# InverterSchematic.net
KiCad netlist of a schematic drawn in Altium Designer
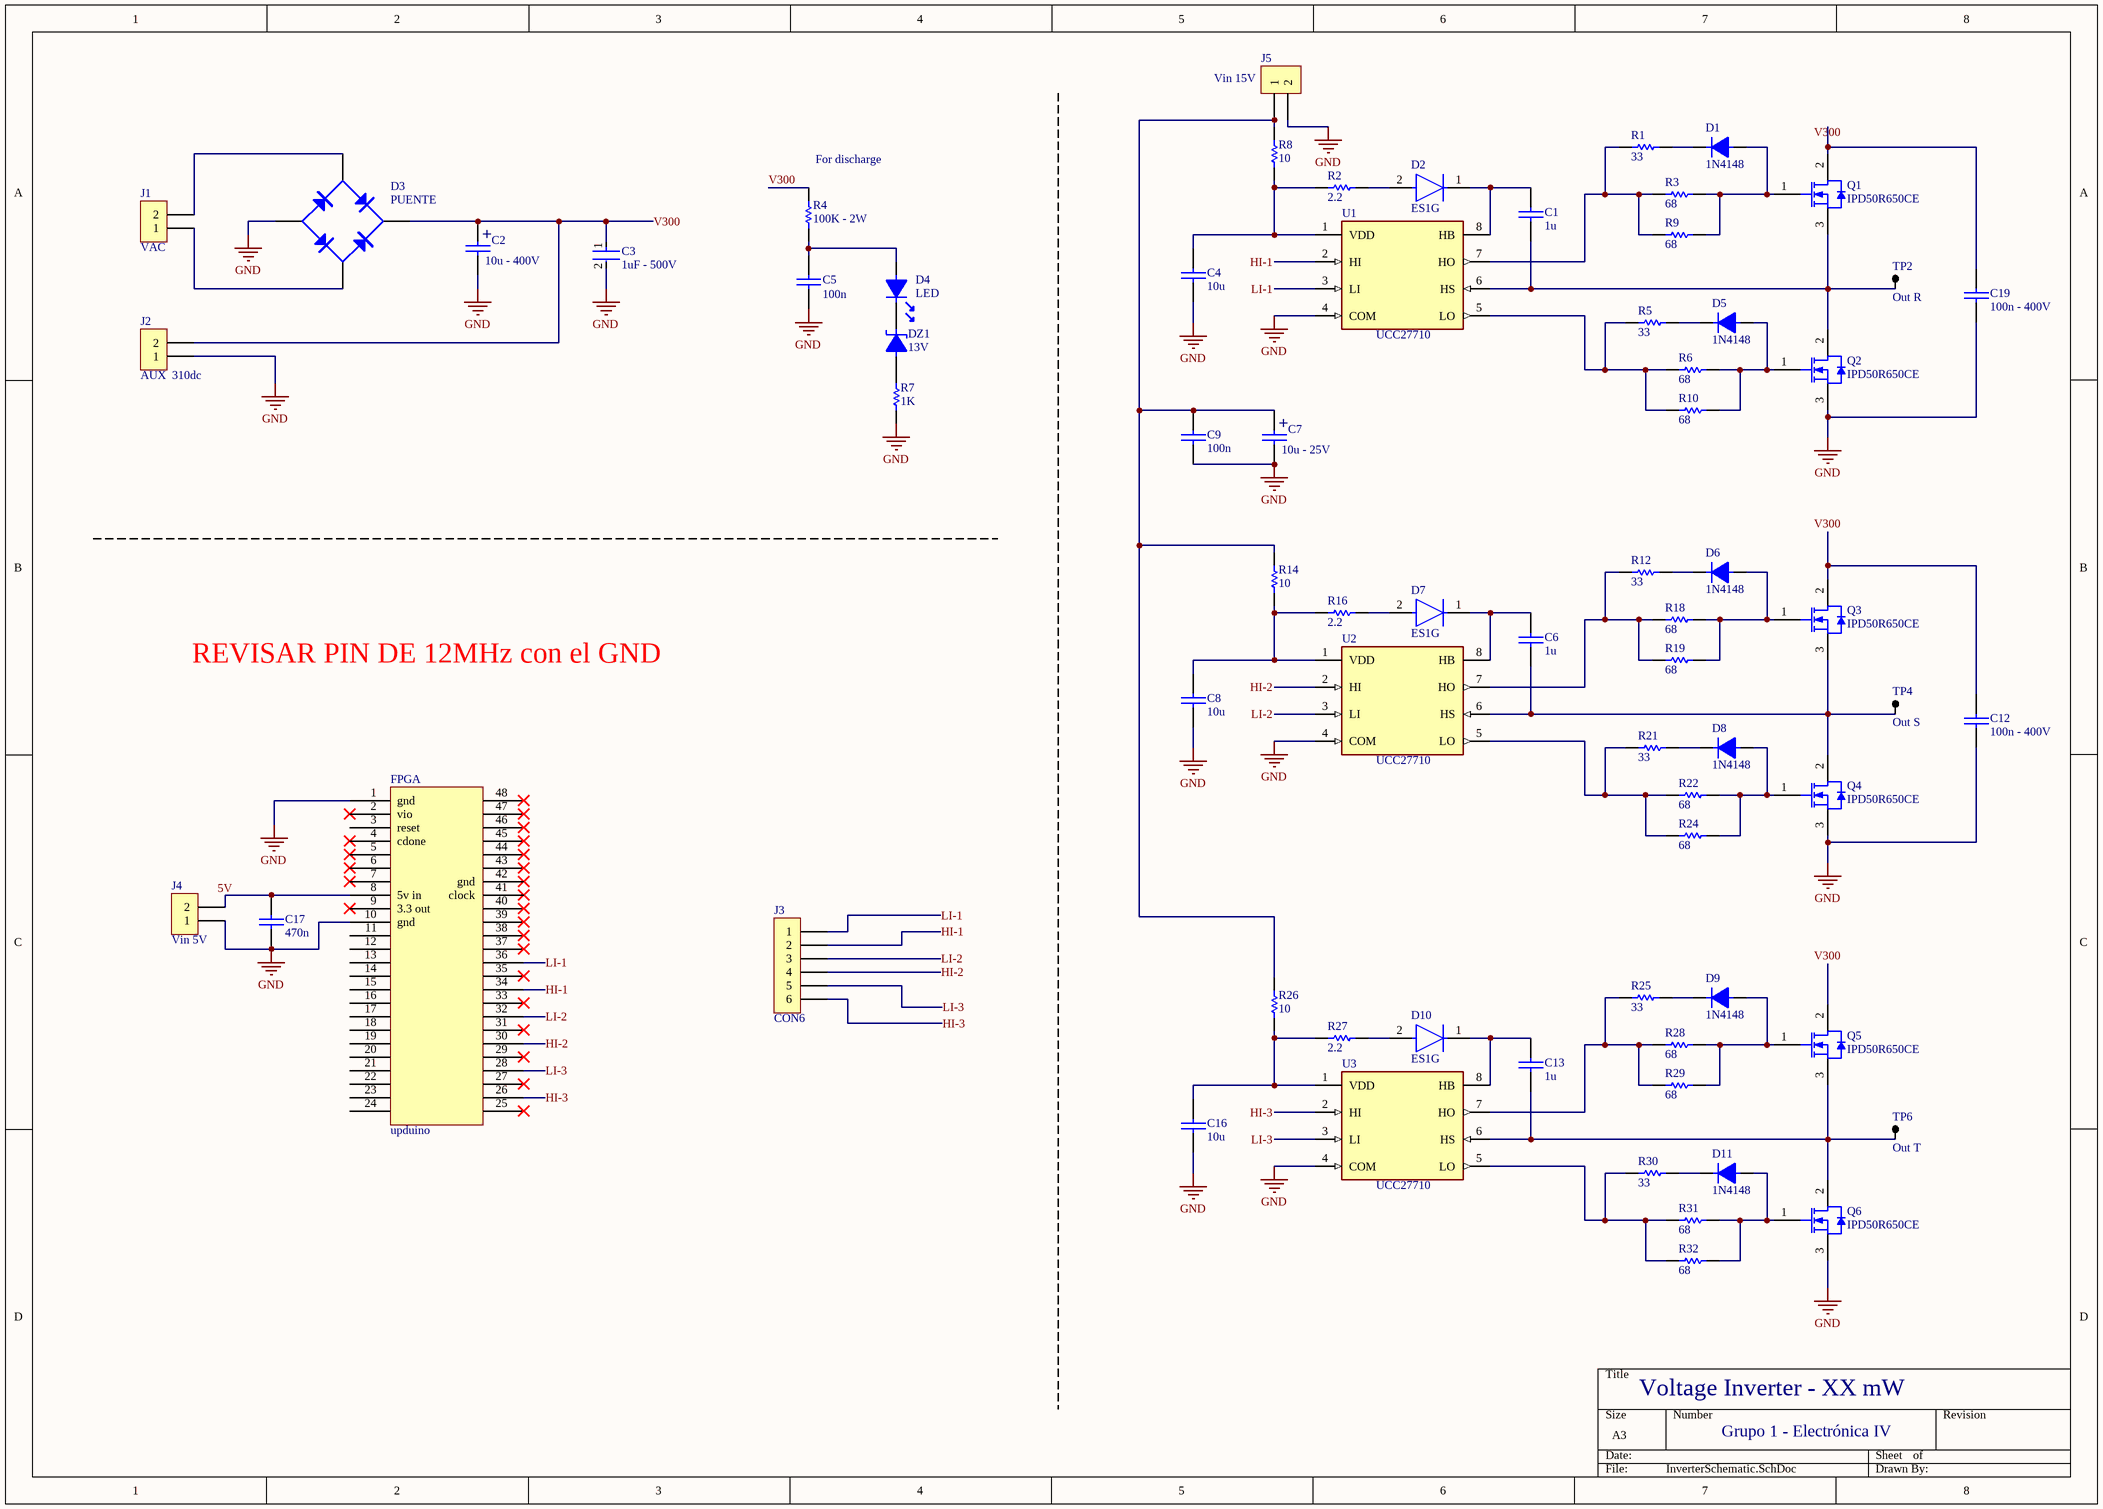
[diagram p0: InverterSchematic.SchDoc]

(export (version "E")
  (design (tool "Eeschema 10.0.6"))
  (components
    (comp (ref "C1") (value "1u") (footprint "0805") (libsource (lib "LIBEBAL") (part "CAP")))
    (comp (ref "C2")
      (value "10u - 400V")
      (footprint "CAP200RP2")
      (libsource (lib "LIBEBAL Tobi") (part "CAPPOL"))
    )
    (comp (ref "C3")
      (value "1uF - 500V")
      (footprint "FP-GRM55D-0_4-IPC_B")
      (description "Chip Multilayer Ceramic Capacitors for General Purpose, 2220, 1.0uF, X7R, 15%, 10%, 500V")
      (fields (field (name "VOLTAGE") "250V") (field (name "TOLERANCE") "10%"))
      (libsource (lib "Altium Content Vault") (part "b4654b650e69147ec39a6b967a45e02"))
    )
    (comp (ref "C4") (value "10u") (footprint "0805") (libsource (lib "LIBEBAL") (part "CAP")))
    (comp (ref "C5") (value "100n") (footprint "0805") (libsource (lib "LIBEBAL Tobi") (part "CAP")))
    (comp (ref "C6") (value "1u") (footprint "0805") (libsource (lib "LIBEBAL") (part "CAP")))
    (comp (ref "C7")
      (value "10u - 25V")
      (footprint "CAP100RP")
      (libsource (lib "LIBEBAL Tobi") (part "CAPPOL"))
    )
    (comp (ref "C8") (value "10u") (footprint "0805") (libsource (lib "LIBEBAL") (part "CAP")))
    (comp (ref "C9") (value "100n") (footprint "CAP200") (libsource (lib "LIBEBAL") (part "CAP")))
    (comp (ref "C12") (value "100n - 400V") (footprint "CAP200") (libsource (lib "LIBEBAL") (part "CAP")))
    (comp (ref "C13") (value "1u") (footprint "0805") (libsource (lib "LIBEBAL") (part "CAP")))
    (comp (ref "C16") (value "10u") (footprint "0805") (libsource (lib "LIBEBAL") (part "CAP")))
    (comp (ref "C17") (value "470n") (footprint "0805") (libsource (lib "LIBEBAL") (part "CAP")))
    (comp (ref "C19") (value "100n - 400V") (footprint "CAP200") (libsource (lib "LIBEBAL") (part "CAP")))
    (comp (ref "D1") (value "1N4148") (footprint "DO41") (libsource (lib "LIBEBAL") (part "DIODO")))
    (comp (ref "D2")
      (value "ES1G")
      (footprint "FP-403AE-MFG")
      (description "DIODE GEN PURP 400V 1A SMA")
      (fields
        (field (name "OCTOPART") "https://octopart.com/es1g-on+semiconductor-84324858")
        (field (name "MANUFACTURER") "ON Semiconductor")
      )
      (libsource (lib "Altium Content Vault") (part "d7152d700b627762746794eb795d46e"))
    )
    (comp (ref "D3")
      (value "PUENTE")
      (footprint "PUENTE - W10M")
      (libsource (lib "LIBEBAL Tobi") (part "PUENTE"))
    )
    (comp (ref "D4") (value "LED") (footprint "LED3") (libsource (lib "LIBEBAL Tobi") (part "LED")))
    (comp (ref "D5") (value "1N4148") (footprint "DO41") (libsource (lib "LIBEBAL") (part "DIODO")))
    (comp (ref "D6") (value "1N4148") (footprint "DO41") (libsource (lib "LIBEBAL") (part "DIODO")))
    (comp (ref "D7")
      (value "ES1G")
      (footprint "FP-403AE-MFG")
      (description "DIODE GEN PURP 400V 1A SMA")
      (fields
        (field (name "OCTOPART") "https://octopart.com/es1g-on+semiconductor-84324858")
        (field (name "MANUFACTURER") "ON Semiconductor")
      )
      (libsource (lib "Altium Content Vault") (part "d7152d700b627762746794eb795d46e"))
    )
    (comp (ref "D8") (value "1N4148") (footprint "DO41") (libsource (lib "LIBEBAL") (part "DIODO")))
    (comp (ref "D9") (value "1N4148") (footprint "DO41") (libsource (lib "LIBEBAL") (part "DIODO")))
    (comp (ref "D10")
      (value "ES1G")
      (footprint "FP-403AE-MFG")
      (description "DIODE GEN PURP 400V 1A SMA")
      (fields
        (field (name "OCTOPART") "https://octopart.com/es1g-on+semiconductor-84324858")
        (field (name "MANUFACTURER") "ON Semiconductor")
      )
      (libsource (lib "Altium Content Vault") (part "d7152d700b627762746794eb795d46e"))
    )
    (comp (ref "D11") (value "1N4148") (footprint "DO41") (libsource (lib "LIBEBAL") (part "DIODO")))
    (comp (ref "DZ1") (value "13V") (footprint "DO41") (libsource (lib "LIBEBAL Tobi") (part "DIODO ZENER")))
    (comp (ref "FPGA")
      (value "upduino")
      (footprint "FPGA")
      (description "upduino v3.0")
      (libsource (lib "InverterSchLib") (part "FPGA"))
    )
    (comp (ref "J1") (value "VAC") (footprint "BORNERA2") (libsource (lib "LIBEBAL Tobi") (part "BORNERA 2")))
    (comp (ref "J2")
      (value "AUX  310dc")
      (footprint "BORNERA2")
      (libsource (lib "LIBEBAL Tobi") (part "BORNERA 2"))
    )
    (comp (ref "J3") (value "CON6") (footprint "SIP6") (libsource (lib "LIBEBAL") (part "CON6")))
    (comp (ref "J4")
      (value "Vin 5V")
      (footprint "SIP2")
      (description "UPDuino Power Input")
      (libsource (lib "LIBEBAL Tobi") (part "CON2"))
    )
    (comp (ref "J5")
      (value "Vin 15V")
      (footprint "SIP2")
      (description "UPDuino Power Input")
      (libsource (lib "") (part "CON2_1"))
    )
    (comp (ref "Q1")
      (value "IPD50R650CE")
      (footprint "INF-PG-TO252-3-313_N")
      (fields (field (name "MANUFACTURER") "Infineon"))
      (libsource (lib "Altium Content Vault") (part "INF-NEMOS-GDS-3"))
    )
    (comp (ref "Q2")
      (value "IPD50R650CE")
      (footprint "INF-PG-TO252-3-313_N")
      (fields (field (name "MANUFACTURER") "Infineon"))
      (libsource (lib "Altium Content Vault") (part "INF-NEMOS-GDS-3"))
    )
    (comp (ref "Q3")
      (value "IPD50R650CE")
      (footprint "INF-PG-TO252-3-313_N")
      (fields (field (name "MANUFACTURER") "Infineon"))
      (libsource (lib "Altium Content Vault") (part "INF-NEMOS-GDS-3"))
    )
    (comp (ref "Q4")
      (value "IPD50R650CE")
      (footprint "INF-PG-TO252-3-313_N")
      (fields (field (name "MANUFACTURER") "Infineon"))
      (libsource (lib "Altium Content Vault") (part "INF-NEMOS-GDS-3"))
    )
    (comp (ref "Q5")
      (value "IPD50R650CE")
      (footprint "INF-PG-TO252-3-313_N")
      (fields (field (name "MANUFACTURER") "Infineon"))
      (libsource (lib "Altium Content Vault") (part "INF-NEMOS-GDS-3"))
    )
    (comp (ref "Q6")
      (value "IPD50R650CE")
      (footprint "INF-PG-TO252-3-313_N")
      (fields (field (name "MANUFACTURER") "Infineon"))
      (libsource (lib "Altium Content Vault") (part "INF-NEMOS-GDS-3"))
    )
    (comp (ref "R1")
      (value "33")
      (footprint "0805")
      (description "33?")
      (libsource (lib "LIBEBAL") (part "RES"))
    )
    (comp (ref "R2") (value "2.2") (footprint "RES300") (libsource (lib "LIBEBAL") (part "RES")))
    (comp (ref "R3") (value "68") (footprint "0805") (libsource (lib "LIBEBAL") (part "RES")))
    (comp (ref "R4") (value "100K - 2W") (footprint "RES300") (libsource (lib "LIBEBAL Tobi") (part "RES")))
    (comp (ref "R5") (value "33") (footprint "0805") (libsource (lib "LIBEBAL") (part "RES")))
    (comp (ref "R6") (value "68") (footprint "0805") (libsource (lib "LIBEBAL") (part "RES")))
    (comp (ref "R7") (value "1K") (footprint "0805") (libsource (lib "LIBEBAL") (part "RES")))
    (comp (ref "R8") (value "10") (footprint "RES300") (libsource (lib "LIBEBAL") (part "RES")))
    (comp (ref "R9") (value "68") (footprint "0805") (libsource (lib "LIBEBAL") (part "RES")))
    (comp (ref "R10") (value "68") (footprint "0805") (libsource (lib "LIBEBAL") (part "RES")))
    (comp (ref "R12")
      (value "33")
      (footprint "0805")
      (description "33?")
      (libsource (lib "LIBEBAL") (part "RES"))
    )
    (comp (ref "R14") (value "10") (footprint "RES300") (libsource (lib "LIBEBAL") (part "RES")))
    (comp (ref "R16") (value "2.2") (footprint "RES300") (libsource (lib "LIBEBAL") (part "RES")))
    (comp (ref "R18") (value "68") (footprint "0805") (libsource (lib "LIBEBAL") (part "RES")))
    (comp (ref "R19") (value "68") (footprint "0805") (libsource (lib "LIBEBAL") (part "RES")))
    (comp (ref "R21") (value "33") (footprint "0805") (libsource (lib "LIBEBAL") (part "RES")))
    (comp (ref "R22") (value "68") (footprint "0805") (libsource (lib "LIBEBAL") (part "RES")))
    (comp (ref "R24") (value "68") (footprint "0805") (libsource (lib "LIBEBAL") (part "RES")))
    (comp (ref "R25")
      (value "33")
      (footprint "0805")
      (description "33?")
      (libsource (lib "LIBEBAL") (part "RES"))
    )
    (comp (ref "R26") (value "10") (footprint "RES300") (libsource (lib "LIBEBAL") (part "RES")))
    (comp (ref "R27") (value "2.2") (footprint "RES300") (libsource (lib "LIBEBAL") (part "RES")))
    (comp (ref "R28") (value "68") (footprint "0805") (libsource (lib "LIBEBAL") (part "RES")))
    (comp (ref "R29") (value "68") (footprint "0805") (libsource (lib "LIBEBAL") (part "RES")))
    (comp (ref "R30") (value "33") (footprint "0805") (libsource (lib "LIBEBAL") (part "RES")))
    (comp (ref "R31") (value "68") (footprint "0805") (libsource (lib "LIBEBAL") (part "RES")))
    (comp (ref "R32") (value "68") (footprint "0805") (libsource (lib "LIBEBAL") (part "RES")))
    (comp (ref "TP2") (value "Out R") (footprint "TPTH") (libsource (lib "LIBEBAL") (part "TP")))
    (comp (ref "TP4") (value "Out S") (footprint "TPTH") (libsource (lib "LIBEBAL") (part "TP")))
    (comp (ref "TP6") (value "Out T") (footprint "TPTH") (libsource (lib "LIBEBAL") (part "TP")))
    (comp (ref "U1")
      (value "UCC27710")
      (footprint "FP-PG-DSO-8-IPC_C")
      (description "GATE DRVR HI/LOW SIDE 8SOIC")
      (libsource (lib "Altium Content Vault") (part "f43bf47bf2763d79e2fe7860ecc000c"))
    )
    (comp (ref "U2")
      (value "UCC27710")
      (footprint "FP-PG-DSO-8-IPC_C")
      (description "GATE DRVR HI/LOW SIDE 8SOIC")
      (libsource (lib "Altium Content Vault") (part "f43bf47bf2763d79e2fe7860ecc000c"))
    )
    (comp (ref "U3")
      (value "UCC27710")
      (footprint "FP-PG-DSO-8-IPC_C")
      (description "GATE DRVR HI/LOW SIDE 8SOIC")
      (libsource (lib "Altium Content Vault") (part "f43bf47bf2763d79e2fe7860ecc000c"))
    )
  )
  (nets
    (net (code "1") (name "/5V") (class "Default")
      (node (ref "C17") (pin "1") (pinfunction "1_1") (pintype "passive"))
      (node (ref "FPGA") (pin "8") (pinfunction "5v_in_8") (pintype "passive"))
      (node (ref "J4") (pin "2") (pinfunction "2_2") (pintype "passive"))
    )
    (net (code "2") (name "/HI-1") (class "Default")
      (node (ref "FPGA") (pin "34") (pintype "passive"))
      (node (ref "J3") (pin "2") (pinfunction "2_2") (pintype "passive"))
      (node (ref "U1") (pin "2") (pinfunction "HI_2") (pintype "input"))
    )
    (net (code "3") (name "/HI-2") (class "Default")
      (node (ref "FPGA") (pin "30") (pintype "passive"))
      (node (ref "J3") (pin "4") (pinfunction "4_4") (pintype "passive"))
      (node (ref "U2") (pin "2") (pinfunction "HI_2") (pintype "input"))
    )
    (net (code "4") (name "/HI-3") (class "Default")
      (node (ref "FPGA") (pin "26") (pintype "passive"))
      (node (ref "J3") (pin "6") (pinfunction "6_6") (pintype "passive"))
      (node (ref "U3") (pin "2") (pinfunction "HI_2") (pintype "input"))
    )
    (net (code "5") (name "/LI-1") (class "Default")
      (node (ref "FPGA") (pin "36") (pintype "passive"))
      (node (ref "J3") (pin "1") (pinfunction "1_1") (pintype "passive"))
      (node (ref "U1") (pin "3") (pinfunction "LI_3") (pintype "input"))
    )
    (net (code "6") (name "/LI-2") (class "Default")
      (node (ref "FPGA") (pin "32") (pintype "passive"))
      (node (ref "J3") (pin "3") (pinfunction "3_3") (pintype "passive"))
      (node (ref "U2") (pin "3") (pinfunction "LI_3") (pintype "input"))
    )
    (net (code "7") (name "/LI-3") (class "Default")
      (node (ref "FPGA") (pin "28") (pintype "passive"))
      (node (ref "J3") (pin "5") (pinfunction "5_5") (pintype "passive"))
      (node (ref "U3") (pin "3") (pinfunction "LI_3") (pintype "input"))
    )
    (net (code "8") (name "/V300") (class "Default")
      (node (ref "C12") (pin "1") (pinfunction "1_1") (pintype "passive"))
      (node (ref "C19") (pin "1") (pinfunction "1_1") (pintype "passive"))
      (node (ref "C2") (pin "1") (pinfunction "1_1") (pintype "passive"))
      (node (ref "C3") (pin "1") (pinfunction "1_1") (pintype "passive"))
      (node (ref "D3") (pin "1") (pinfunction "V+_1") (pintype "passive"))
      (node (ref "J2") (pin "2") (pinfunction "2_2") (pintype "passive"))
      (node (ref "Q1") (pin "2") (pinfunction "DRAIN_2") (pintype "passive"))
      (node (ref "Q3") (pin "2") (pinfunction "DRAIN_2") (pintype "passive"))
      (node (ref "Q5") (pin "2") (pinfunction "DRAIN_2") (pintype "passive"))
      (node (ref "R4") (pin "2") (pinfunction "2_2") (pintype "passive"))
    )
    (net (code "9") (name "GND") (class "Default")
      (node (ref "C12") (pin "2") (pinfunction "2_2") (pintype "passive"))
      (node (ref "C16") (pin "2") (pinfunction "2_2") (pintype "passive"))
      (node (ref "C17") (pin "2") (pinfunction "2_2") (pintype "passive"))
      (node (ref "C19") (pin "2") (pinfunction "2_2") (pintype "passive"))
      (node (ref "C2") (pin "2") (pinfunction "2_2") (pintype "passive"))
      (node (ref "C3") (pin "2") (pinfunction "2_2") (pintype "passive"))
      (node (ref "C4") (pin "2") (pinfunction "2_2") (pintype "passive"))
      (node (ref "C5") (pin "1") (pinfunction "1_1") (pintype "passive"))
      (node (ref "C7") (pin "2") (pinfunction "2_2") (pintype "passive"))
      (node (ref "C8") (pin "2") (pinfunction "2_2") (pintype "passive"))
      (node (ref "C9") (pin "2") (pinfunction "2_2") (pintype "passive"))
      (node (ref "D3") (pin "3") (pinfunction "V-_3") (pintype "passive"))
      (node (ref "FPGA") (pin "1") (pinfunction "gnd_1") (pintype "passive"))
      (node (ref "FPGA") (pin "10") (pinfunction "gnd_10") (pintype "passive"))
      (node (ref "J2") (pin "1") (pinfunction "1_1") (pintype "passive"))
      (node (ref "J4") (pin "1") (pinfunction "1_1") (pintype "passive"))
      (node (ref "J5") (pin "2") (pinfunction "2_2") (pintype "passive"))
      (node (ref "Q2") (pin "3") (pinfunction "SOURCE_3") (pintype "passive"))
      (node (ref "Q4") (pin "3") (pinfunction "SOURCE_3") (pintype "passive"))
      (node (ref "Q6") (pin "3") (pinfunction "SOURCE_3") (pintype "passive"))
      (node (ref "R7") (pin "2") (pinfunction "2_2") (pintype "passive"))
      (node (ref "U1") (pin "4") (pinfunction "COM_4") (pintype "input"))
      (node (ref "U2") (pin "4") (pinfunction "COM_4") (pintype "input"))
      (node (ref "U3") (pin "4") (pinfunction "COM_4") (pintype "input"))
    )
    (net (code "10") (name "Net-(C5-Pad2)") (class "Default")
      (node (ref "C5") (pin "2") (pinfunction "2_2") (pintype "passive"))
      (node (ref "D4") (pin "1") (pinfunction "1_1") (pintype "passive"))
      (node (ref "R4") (pin "1") (pinfunction "1_1") (pintype "passive"))
    )
    (net (code "11") (name "Net-(C7-Pad1)") (class "Default")
      (node (ref "C7") (pin "1") (pinfunction "1_1") (pintype "passive"))
      (node (ref "C9") (pin "1") (pinfunction "1_1") (pintype "passive"))
      (node (ref "J5") (pin "1") (pinfunction "1_1") (pintype "passive"))
      (node (ref "R14") (pin "2") (pinfunction "2_2") (pintype "passive"))
      (node (ref "R26") (pin "2") (pinfunction "2_2") (pintype "passive"))
      (node (ref "R8") (pin "2") (pinfunction "2_2") (pintype "passive"))
    )
    (net (code "12") (name "Net-(D1-Pad2)") (class "Default")
      (node (ref "D1") (pin "2") (pinfunction "2_2") (pintype "passive"))
      (node (ref "R1") (pin "2") (pinfunction "2_2") (pintype "passive"))
    )
    (net (code "13") (name "Net-(D2-A)") (class "Default")
      (node (ref "D2") (pin "2") (pinfunction "A_2") (pintype "passive"))
      (node (ref "R2") (pin "2") (pinfunction "2_2") (pintype "passive"))
    )
    (net (code "14") (name "Net-(D2-C)") (class "Default")
      (node (ref "C1") (pin "1") (pinfunction "1_1") (pintype "passive"))
      (node (ref "D2") (pin "1") (pinfunction "C_1") (pintype "passive"))
      (node (ref "U1") (pin "8") (pinfunction "HB_8") (pintype "passive"))
    )
    (net (code "15") (name "Net-(D3-AC-Pad2)") (class "Default")
      (node (ref "D3") (pin "2") (pinfunction "AC_2") (pintype "passive"))
      (node (ref "J1") (pin "2") (pinfunction "2_2") (pintype "passive"))
    )
    (net (code "16") (name "Net-(D3-AC-Pad4)") (class "Default")
      (node (ref "D3") (pin "4") (pinfunction "AC_4") (pintype "passive"))
      (node (ref "J1") (pin "1") (pinfunction "1_1") (pintype "passive"))
    )
    (net (code "17") (name "Net-(D4-Pad2)") (class "Default")
      (node (ref "D4") (pin "2") (pinfunction "2_2") (pintype "passive"))
      (node (ref "DZ1") (pin "2") (pinfunction "2_2") (pintype "passive"))
    )
    (net (code "18") (name "Net-(D5-Pad2)") (class "Default")
      (node (ref "D5") (pin "2") (pinfunction "2_2") (pintype "passive"))
      (node (ref "R5") (pin "2") (pinfunction "2_2") (pintype "passive"))
    )
    (net (code "19") (name "Net-(D6-Pad2)") (class "Default")
      (node (ref "D6") (pin "2") (pinfunction "2_2") (pintype "passive"))
      (node (ref "R12") (pin "2") (pinfunction "2_2") (pintype "passive"))
    )
    (net (code "20") (name "Net-(D7-A)") (class "Default")
      (node (ref "D7") (pin "2") (pinfunction "A_2") (pintype "passive"))
      (node (ref "R16") (pin "2") (pinfunction "2_2") (pintype "passive"))
    )
    (net (code "21") (name "Net-(D7-C)") (class "Default")
      (node (ref "C6") (pin "1") (pinfunction "1_1") (pintype "passive"))
      (node (ref "D7") (pin "1") (pinfunction "C_1") (pintype "passive"))
      (node (ref "U2") (pin "8") (pinfunction "HB_8") (pintype "passive"))
    )
    (net (code "22") (name "Net-(D8-Pad2)") (class "Default")
      (node (ref "D8") (pin "2") (pinfunction "2_2") (pintype "passive"))
      (node (ref "R21") (pin "2") (pinfunction "2_2") (pintype "passive"))
    )
    (net (code "23") (name "Net-(D9-Pad2)") (class "Default")
      (node (ref "D9") (pin "2") (pinfunction "2_2") (pintype "passive"))
      (node (ref "R25") (pin "2") (pinfunction "2_2") (pintype "passive"))
    )
    (net (code "24") (name "Net-(D10-A)") (class "Default")
      (node (ref "D10") (pin "2") (pinfunction "A_2") (pintype "passive"))
      (node (ref "R27") (pin "2") (pinfunction "2_2") (pintype "passive"))
    )
    (net (code "25") (name "Net-(D10-C)") (class "Default")
      (node (ref "C13") (pin "1") (pinfunction "1_1") (pintype "passive"))
      (node (ref "D10") (pin "1") (pinfunction "C_1") (pintype "passive"))
      (node (ref "U3") (pin "8") (pinfunction "HB_8") (pintype "passive"))
    )
    (net (code "26") (name "Net-(D11-Pad2)") (class "Default")
      (node (ref "D11") (pin "2") (pinfunction "2_2") (pintype "passive"))
      (node (ref "R30") (pin "2") (pinfunction "2_2") (pintype "passive"))
    )
    (net (code "27") (name "Net-(DZ1-Pad1)") (class "Default")
      (node (ref "DZ1") (pin "1") (pinfunction "1_1") (pintype "passive"))
      (node (ref "R7") (pin "1") (pinfunction "1_1") (pintype "passive"))
    )
    (net (code "28") (name "Net-(Q1-GATE)") (class "Default")
      (node (ref "D1") (pin "1") (pinfunction "1_1") (pintype "passive"))
      (node (ref "Q1") (pin "1") (pinfunction "GATE_1") (pintype "passive"))
      (node (ref "R3") (pin "2") (pinfunction "2_2") (pintype "passive"))
      (node (ref "R9") (pin "2") (pinfunction "2_2") (pintype "passive"))
    )
    (net (code "29") (name "Net-(Q1-SOURCE)") (class "Default")
      (node (ref "C1") (pin "2") (pinfunction "2_2") (pintype "passive"))
      (node (ref "Q1") (pin "3") (pinfunction "SOURCE_3") (pintype "passive"))
      (node (ref "Q2") (pin "2") (pinfunction "DRAIN_2") (pintype "passive"))
      (node (ref "TP2") (pin "1") (pinfunction "1_1") (pintype "passive"))
      (node (ref "U1") (pin "6") (pinfunction "HS_6") (pintype "input"))
    )
    (net (code "30") (name "Net-(Q2-GATE)") (class "Default")
      (node (ref "D5") (pin "1") (pinfunction "1_1") (pintype "passive"))
      (node (ref "Q2") (pin "1") (pinfunction "GATE_1") (pintype "passive"))
      (node (ref "R10") (pin "2") (pinfunction "2_2") (pintype "passive"))
      (node (ref "R6") (pin "2") (pinfunction "2_2") (pintype "passive"))
    )
    (net (code "31") (name "Net-(Q3-GATE)") (class "Default")
      (node (ref "D6") (pin "1") (pinfunction "1_1") (pintype "passive"))
      (node (ref "Q3") (pin "1") (pinfunction "GATE_1") (pintype "passive"))
      (node (ref "R18") (pin "2") (pinfunction "2_2") (pintype "passive"))
      (node (ref "R19") (pin "2") (pinfunction "2_2") (pintype "passive"))
    )
    (net (code "32") (name "Net-(Q3-SOURCE)") (class "Default")
      (node (ref "C6") (pin "2") (pinfunction "2_2") (pintype "passive"))
      (node (ref "Q3") (pin "3") (pinfunction "SOURCE_3") (pintype "passive"))
      (node (ref "Q4") (pin "2") (pinfunction "DRAIN_2") (pintype "passive"))
      (node (ref "TP4") (pin "1") (pinfunction "1_1") (pintype "passive"))
      (node (ref "U2") (pin "6") (pinfunction "HS_6") (pintype "input"))
    )
    (net (code "33") (name "Net-(Q4-GATE)") (class "Default")
      (node (ref "D8") (pin "1") (pinfunction "1_1") (pintype "passive"))
      (node (ref "Q4") (pin "1") (pinfunction "GATE_1") (pintype "passive"))
      (node (ref "R22") (pin "2") (pinfunction "2_2") (pintype "passive"))
      (node (ref "R24") (pin "2") (pinfunction "2_2") (pintype "passive"))
    )
    (net (code "34") (name "Net-(Q5-GATE)") (class "Default")
      (node (ref "D9") (pin "1") (pinfunction "1_1") (pintype "passive"))
      (node (ref "Q5") (pin "1") (pinfunction "GATE_1") (pintype "passive"))
      (node (ref "R28") (pin "2") (pinfunction "2_2") (pintype "passive"))
      (node (ref "R29") (pin "2") (pinfunction "2_2") (pintype "passive"))
    )
    (net (code "35") (name "Net-(Q5-SOURCE)") (class "Default")
      (node (ref "C13") (pin "2") (pinfunction "2_2") (pintype "passive"))
      (node (ref "Q5") (pin "3") (pinfunction "SOURCE_3") (pintype "passive"))
      (node (ref "Q6") (pin "2") (pinfunction "DRAIN_2") (pintype "passive"))
      (node (ref "TP6") (pin "1") (pinfunction "1_1") (pintype "passive"))
      (node (ref "U3") (pin "6") (pinfunction "HS_6") (pintype "input"))
    )
    (net (code "36") (name "Net-(Q6-GATE)") (class "Default")
      (node (ref "D11") (pin "1") (pinfunction "1_1") (pintype "passive"))
      (node (ref "Q6") (pin "1") (pinfunction "GATE_1") (pintype "passive"))
      (node (ref "R31") (pin "2") (pinfunction "2_2") (pintype "passive"))
      (node (ref "R32") (pin "2") (pinfunction "2_2") (pintype "passive"))
    )
    (net (code "37") (name "Net-(U1-HO)") (class "Default")
      (node (ref "R1") (pin "1") (pinfunction "1_1") (pintype "passive"))
      (node (ref "R3") (pin "1") (pinfunction "1_1") (pintype "passive"))
      (node (ref "R9") (pin "1") (pinfunction "1_1") (pintype "passive"))
      (node (ref "U1") (pin "7") (pinfunction "HO_7") (pintype "output"))
    )
    (net (code "38") (name "Net-(U1-LO)") (class "Default")
      (node (ref "R10") (pin "1") (pinfunction "1_1") (pintype "passive"))
      (node (ref "R5") (pin "1") (pinfunction "1_1") (pintype "passive"))
      (node (ref "R6") (pin "1") (pinfunction "1_1") (pintype "passive"))
      (node (ref "U1") (pin "5") (pinfunction "LO_5") (pintype "output"))
    )
    (net (code "39") (name "Net-(U1-VDD)") (class "Default")
      (node (ref "C4") (pin "1") (pinfunction "1_1") (pintype "passive"))
      (node (ref "R2") (pin "1") (pinfunction "1_1") (pintype "passive"))
      (node (ref "R8") (pin "1") (pinfunction "1_1") (pintype "passive"))
      (node (ref "U1") (pin "1") (pinfunction "VDD_1") (pintype "power_in"))
    )
    (net (code "40") (name "Net-(U2-HO)") (class "Default")
      (node (ref "R12") (pin "1") (pinfunction "1_1") (pintype "passive"))
      (node (ref "R18") (pin "1") (pinfunction "1_1") (pintype "passive"))
      (node (ref "R19") (pin "1") (pinfunction "1_1") (pintype "passive"))
      (node (ref "U2") (pin "7") (pinfunction "HO_7") (pintype "output"))
    )
    (net (code "41") (name "Net-(U2-LO)") (class "Default")
      (node (ref "R21") (pin "1") (pinfunction "1_1") (pintype "passive"))
      (node (ref "R22") (pin "1") (pinfunction "1_1") (pintype "passive"))
      (node (ref "R24") (pin "1") (pinfunction "1_1") (pintype "passive"))
      (node (ref "U2") (pin "5") (pinfunction "LO_5") (pintype "output"))
    )
    (net (code "42") (name "Net-(U2-VDD)") (class "Default")
      (node (ref "C8") (pin "1") (pinfunction "1_1") (pintype "passive"))
      (node (ref "R14") (pin "1") (pinfunction "1_1") (pintype "passive"))
      (node (ref "R16") (pin "1") (pinfunction "1_1") (pintype "passive"))
      (node (ref "U2") (pin "1") (pinfunction "VDD_1") (pintype "power_in"))
    )
    (net (code "43") (name "Net-(U3-HO)") (class "Default")
      (node (ref "R25") (pin "1") (pinfunction "1_1") (pintype "passive"))
      (node (ref "R28") (pin "1") (pinfunction "1_1") (pintype "passive"))
      (node (ref "R29") (pin "1") (pinfunction "1_1") (pintype "passive"))
      (node (ref "U3") (pin "7") (pinfunction "HO_7") (pintype "output"))
    )
    (net (code "44") (name "Net-(U3-LO)") (class "Default")
      (node (ref "R30") (pin "1") (pinfunction "1_1") (pintype "passive"))
      (node (ref "R31") (pin "1") (pinfunction "1_1") (pintype "passive"))
      (node (ref "R32") (pin "1") (pinfunction "1_1") (pintype "passive"))
      (node (ref "U3") (pin "5") (pinfunction "LO_5") (pintype "output"))
    )
    (net (code "45") (name "Net-(U3-VDD)") (class "Default")
      (node (ref "C16") (pin "1") (pinfunction "1_1") (pintype "passive"))
      (node (ref "R26") (pin "1") (pinfunction "1_1") (pintype "passive"))
      (node (ref "R27") (pin "1") (pinfunction "1_1") (pintype "passive"))
      (node (ref "U3") (pin "1") (pinfunction "VDD_1") (pintype "power_in"))
    )
    (net (code "46") (name "unconnected-(FPGA-3.3_out-Pad9)") (class "Default")
      (node (ref "FPGA") (pin "9") (pinfunction "3.3_out_9") (pintype "passive+no_connect"))
    )
    (net (code "47") (name "unconnected-(FPGA-Pad5)") (class "Default")
      (node (ref "FPGA") (pin "5") (pintype "passive+no_connect"))
    )
    (net (code "48") (name "unconnected-(FPGA-Pad6)") (class "Default")
      (node (ref "FPGA") (pin "6") (pintype "passive+no_connect"))
    )
    (net (code "49") (name "unconnected-(FPGA-Pad7)") (class "Default")
      (node (ref "FPGA") (pin "7") (pintype "passive+no_connect"))
    )
    (net (code "50") (name "unconnected-(FPGA-Pad11)") (class "Default")
      (node (ref "FPGA") (pin "11") (pintype "passive"))
    )
    (net (code "51") (name "unconnected-(FPGA-Pad12)") (class "Default")
      (node (ref "FPGA") (pin "12") (pintype "passive"))
    )
    (net (code "52") (name "unconnected-(FPGA-Pad13)") (class "Default")
      (node (ref "FPGA") (pin "13") (pintype "passive"))
    )
    (net (code "53") (name "unconnected-(FPGA-Pad14)") (class "Default")
      (node (ref "FPGA") (pin "14") (pintype "passive"))
    )
    (net (code "54") (name "unconnected-(FPGA-Pad15)") (class "Default")
      (node (ref "FPGA") (pin "15") (pintype "passive"))
    )
    (net (code "55") (name "unconnected-(FPGA-Pad16)") (class "Default")
      (node (ref "FPGA") (pin "16") (pintype "passive"))
    )
    (net (code "56") (name "unconnected-(FPGA-Pad17)") (class "Default")
      (node (ref "FPGA") (pin "17") (pintype "passive"))
    )
    (net (code "57") (name "unconnected-(FPGA-Pad18)") (class "Default")
      (node (ref "FPGA") (pin "18") (pintype "passive"))
    )
    (net (code "58") (name "unconnected-(FPGA-Pad19)") (class "Default")
      (node (ref "FPGA") (pin "19") (pintype "passive"))
    )
    (net (code "59") (name "unconnected-(FPGA-Pad20)") (class "Default")
      (node (ref "FPGA") (pin "20") (pintype "passive"))
    )
    (net (code "60") (name "unconnected-(FPGA-Pad21)") (class "Default")
      (node (ref "FPGA") (pin "21") (pintype "passive"))
    )
    (net (code "61") (name "unconnected-(FPGA-Pad22)") (class "Default")
      (node (ref "FPGA") (pin "22") (pintype "passive"))
    )
    (net (code "62") (name "unconnected-(FPGA-Pad23)") (class "Default")
      (node (ref "FPGA") (pin "23") (pintype "passive"))
    )
    (net (code "63") (name "unconnected-(FPGA-Pad24)") (class "Default")
      (node (ref "FPGA") (pin "24") (pintype "passive"))
    )
    (net (code "64") (name "unconnected-(FPGA-Pad25)") (class "Default")
      (node (ref "FPGA") (pin "25") (pintype "passive+no_connect"))
    )
    (net (code "65") (name "unconnected-(FPGA-Pad27)") (class "Default")
      (node (ref "FPGA") (pin "27") (pintype "passive+no_connect"))
    )
    (net (code "66") (name "unconnected-(FPGA-Pad29)") (class "Default")
      (node (ref "FPGA") (pin "29") (pintype "passive+no_connect"))
    )
    (net (code "67") (name "unconnected-(FPGA-Pad31)") (class "Default")
      (node (ref "FPGA") (pin "31") (pintype "passive+no_connect"))
    )
    (net (code "68") (name "unconnected-(FPGA-Pad33)") (class "Default")
      (node (ref "FPGA") (pin "33") (pintype "passive+no_connect"))
    )
    (net (code "69") (name "unconnected-(FPGA-Pad35)") (class "Default")
      (node (ref "FPGA") (pin "35") (pintype "passive+no_connect"))
    )
    (net (code "70") (name "unconnected-(FPGA-Pad37)") (class "Default")
      (node (ref "FPGA") (pin "37") (pintype "passive+no_connect"))
    )
    (net (code "71") (name "unconnected-(FPGA-Pad38)") (class "Default")
      (node (ref "FPGA") (pin "38") (pintype "passive+no_connect"))
    )
    (net (code "72") (name "unconnected-(FPGA-Pad39)") (class "Default")
      (node (ref "FPGA") (pin "39") (pintype "passive+no_connect"))
    )
    (net (code "73") (name "unconnected-(FPGA-Pad40)") (class "Default")
      (node (ref "FPGA") (pin "40") (pintype "passive+no_connect"))
    )
    (net (code "74") (name "unconnected-(FPGA-Pad43)") (class "Default")
      (node (ref "FPGA") (pin "43") (pintype "passive+no_connect"))
    )
    (net (code "75") (name "unconnected-(FPGA-Pad44)") (class "Default")
      (node (ref "FPGA") (pin "44") (pintype "passive+no_connect"))
    )
    (net (code "76") (name "unconnected-(FPGA-Pad45)") (class "Default")
      (node (ref "FPGA") (pin "45") (pintype "passive+no_connect"))
    )
    (net (code "77") (name "unconnected-(FPGA-Pad46)") (class "Default")
      (node (ref "FPGA") (pin "46") (pintype "passive+no_connect"))
    )
    (net (code "78") (name "unconnected-(FPGA-Pad47)") (class "Default")
      (node (ref "FPGA") (pin "47") (pintype "passive+no_connect"))
    )
    (net (code "79") (name "unconnected-(FPGA-Pad48)") (class "Default")
      (node (ref "FPGA") (pin "48") (pintype "passive+no_connect"))
    )
    (net (code "80") (name "unconnected-(FPGA-cdone-Pad4)") (class "Default")
      (node (ref "FPGA") (pin "4") (pinfunction "cdone_4") (pintype "passive+no_connect"))
    )
    (net (code "81") (name "unconnected-(FPGA-clock-Pad41)") (class "Default")
      (node (ref "FPGA") (pin "41") (pinfunction "clock_41") (pintype "passive+no_connect"))
    )
    (net (code "82") (name "unconnected-(FPGA-gnd-Pad42)") (class "Default")
      (node (ref "FPGA") (pin "42") (pinfunction "gnd_42") (pintype "passive+no_connect"))
    )
    (net (code "83") (name "unconnected-(FPGA-reset-Pad3)") (class "Default")
      (node (ref "FPGA") (pin "3") (pinfunction "reset_3") (pintype "passive"))
    )
    (net (code "84") (name "unconnected-(FPGA-vio-Pad2)") (class "Default")
      (node (ref "FPGA") (pin "2") (pinfunction "vio_2") (pintype "passive+no_connect"))
    )
  )
)
